# POV.net
KiCad netlist of a schematic drawn in EAGLE
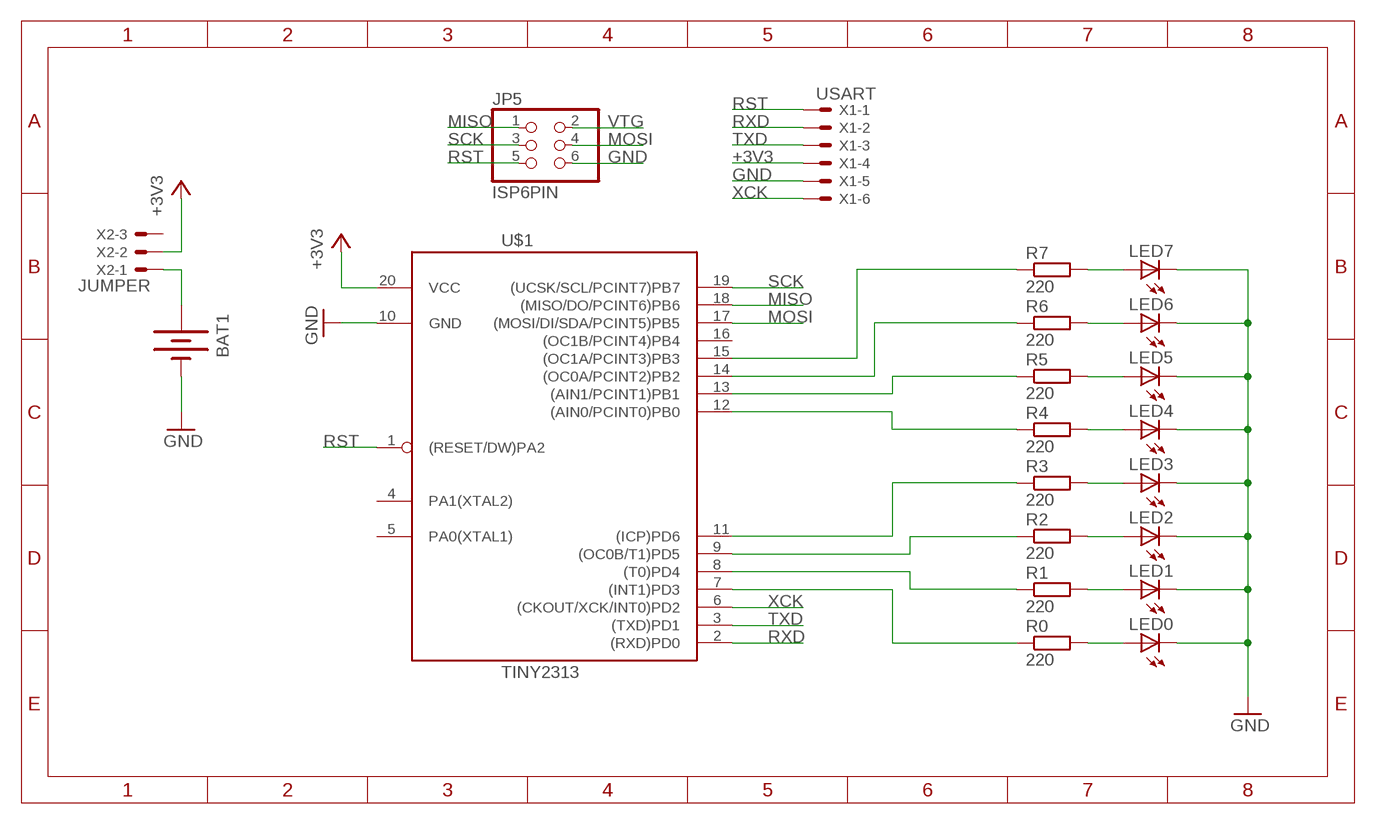
[diagram p0: schematic, sheet 1]

(export (version "E")
  (design (tool "Eeschema 10.0.6"))
  (components
    (comp (ref "BAT1")
      (value "BATTERY20PTH")
      (footprint "eagle-import:BATTCOM_20MM_PTH")
      (libsource (lib "eagle-import") (part "BATTERY20PTH"))
    )
    (comp (ref "JP5")
      (value "ISP6PIN")
      (footprint "eagle-import:2X03")
      (libsource (lib "eagle-import") (part "PINHD-2X3"))
    )
    (comp (ref "LED0")
      (value "LED3MM")
      (footprint "eagle-import:LED3MM")
      (libsource (lib "eagle-import") (part "LED3MM"))
    )
    (comp (ref "LED1")
      (value "LED3MM")
      (footprint "eagle-import:LED3MM")
      (libsource (lib "eagle-import") (part "LED3MM"))
    )
    (comp (ref "LED2")
      (value "LED3MM")
      (footprint "eagle-import:LED3MM")
      (libsource (lib "eagle-import") (part "LED3MM"))
    )
    (comp (ref "LED3")
      (value "LED3MM")
      (footprint "eagle-import:LED3MM")
      (libsource (lib "eagle-import") (part "LED3MM"))
    )
    (comp (ref "LED4")
      (value "LED3MM")
      (footprint "eagle-import:LED3MM")
      (libsource (lib "eagle-import") (part "LED3MM"))
    )
    (comp (ref "LED5")
      (value "LED3MM")
      (footprint "eagle-import:LED3MM")
      (libsource (lib "eagle-import") (part "LED3MM"))
    )
    (comp (ref "LED6")
      (value "LED3MM")
      (footprint "eagle-import:LED3MM")
      (libsource (lib "eagle-import") (part "LED3MM"))
    )
    (comp (ref "LED7")
      (value "LED3MM")
      (footprint "eagle-import:LED3MM")
      (libsource (lib "eagle-import") (part "LED3MM"))
    )
    (comp (ref "R0")
      (value "220")
      (footprint "eagle-import:0207_10")
      (libsource (lib "eagle-import") (part "R-EU_0207/10"))
    )
    (comp (ref "R1")
      (value "220")
      (footprint "eagle-import:0207_10")
      (libsource (lib "eagle-import") (part "R-EU_0207/10"))
    )
    (comp (ref "R2")
      (value "220")
      (footprint "eagle-import:0207_10")
      (libsource (lib "eagle-import") (part "R-EU_0207/10"))
    )
    (comp (ref "R3")
      (value "220")
      (footprint "eagle-import:0207_10")
      (libsource (lib "eagle-import") (part "R-EU_0207/10"))
    )
    (comp (ref "R4")
      (value "220")
      (footprint "eagle-import:0207_10")
      (libsource (lib "eagle-import") (part "R-EU_0207/10"))
    )
    (comp (ref "R5")
      (value "220")
      (footprint "eagle-import:0207_10")
      (libsource (lib "eagle-import") (part "R-EU_0207/10"))
    )
    (comp (ref "R6")
      (value "220")
      (footprint "eagle-import:0207_10")
      (libsource (lib "eagle-import") (part "R-EU_0207/10"))
    )
    (comp (ref "R7")
      (value "220")
      (footprint "eagle-import:0207_10")
      (libsource (lib "eagle-import") (part "R-EU_0207/10"))
    )
    (comp (ref "U$1")
      (value "TINY2313")
      (footprint "eagle-import:DIL20")
      (libsource (lib "eagle-import") (part "TINY2313"))
    )
    (comp (ref "X1")
      (value "USART")
      (footprint "eagle-import:22-23-2061")
      (fields (field (name "MF") "MOLEX") (field (name "MPN") "22-23-2061"))
      (libsource (lib "eagle-import") (part "22-23-2061"))
    )
    (comp (ref "X2")
      (value "JUMPER")
      (footprint "eagle-import:22-23-2031")
      (fields (field (name "MF") "MOLEX") (field (name "MPN") "22-23-2031"))
      (libsource (lib "eagle-import") (part "22-23-2031"))
    )
  )
  (nets
    (net (code "1") (name "+3V3") (class "Default")
      (node (ref "U$1") (pin "20") (pinfunction "VCC_20") (pintype "power_in"))
      (node (ref "X1") (pin "4") (pinfunction "S_4") (pintype "passive"))
      (node (ref "X2") (pin "2") (pinfunction "S_2") (pintype "passive"))
    )
    (net (code "2") (name "/MISO") (class "Default")
      (node (ref "JP5") (pin "1") (pinfunction "1_1") (pintype "passive"))
      (node (ref "U$1") (pin "18") (pinfunction "(MISO/DO/PCINT6)PB6_18") (pintype "bidirectional"))
    )
    (net (code "3") (name "/MOSI") (class "Default")
      (node (ref "JP5") (pin "4") (pinfunction "4_4") (pintype "passive"))
      (node (ref "U$1") (pin "17") (pinfunction "(MOSI/DI/SDA/PCINT5)PB5_17") (pintype "bidirectional"))
    )
    (net (code "4") (name "/RST") (class "Default")
      (node (ref "JP5") (pin "5") (pinfunction "5_5") (pintype "passive"))
      (node (ref "U$1") (pin "1") (pinfunction "(RESET/DW)PA2_1") (pintype "input"))
      (node (ref "X1") (pin "1") (pinfunction "S_1") (pintype "passive"))
    )
    (net (code "5") (name "/RXD") (class "Default")
      (node (ref "U$1") (pin "2") (pinfunction "(RXD)PD0_2") (pintype "bidirectional"))
      (node (ref "X1") (pin "2") (pinfunction "S_2") (pintype "passive"))
    )
    (net (code "6") (name "/SCK") (class "Default")
      (node (ref "JP5") (pin "3") (pinfunction "3_3") (pintype "passive"))
      (node (ref "U$1") (pin "19") (pinfunction "(UCSK/SCL/PCINT7)PB7_19") (pintype "bidirectional"))
    )
    (net (code "7") (name "/TXD") (class "Default")
      (node (ref "U$1") (pin "3") (pinfunction "(TXD)PD1_3") (pintype "bidirectional"))
      (node (ref "X1") (pin "3") (pinfunction "S_3") (pintype "passive"))
    )
    (net (code "8") (name "/VTG") (class "Default")
      (node (ref "JP5") (pin "2") (pinfunction "2_2") (pintype "passive"))
    )
    (net (code "9") (name "/XCK") (class "Default")
      (node (ref "U$1") (pin "6") (pinfunction "(CKOUT/XCK/INT0)PD2_6") (pintype "bidirectional"))
      (node (ref "X1") (pin "6") (pinfunction "S_6") (pintype "passive"))
    )
    (net (code "10") (name "GND") (class "Default")
      (node (ref "BAT1") (pin "2") (pinfunction "-_2") (pintype "power_in"))
      (node (ref "JP5") (pin "6") (pinfunction "6_6") (pintype "passive"))
      (node (ref "LED0") (pin "K") (pinfunction "C_K") (pintype "passive"))
      (node (ref "LED1") (pin "K") (pinfunction "C_K") (pintype "passive"))
      (node (ref "LED2") (pin "K") (pinfunction "C_K") (pintype "passive"))
      (node (ref "LED3") (pin "K") (pinfunction "C_K") (pintype "passive"))
      (node (ref "LED4") (pin "K") (pinfunction "C_K") (pintype "passive"))
      (node (ref "LED5") (pin "K") (pinfunction "C_K") (pintype "passive"))
      (node (ref "LED6") (pin "K") (pinfunction "C_K") (pintype "passive"))
      (node (ref "LED7") (pin "K") (pinfunction "C_K") (pintype "passive"))
      (node (ref "U$1") (pin "10") (pinfunction "GND_10") (pintype "power_in"))
      (node (ref "X1") (pin "5") (pinfunction "S_5") (pintype "passive"))
    )
    (net (code "11") (name "Net-(BAT1-+)") (class "Default")
      (node (ref "BAT1") (pin "1") (pinfunction "+_1") (pintype "power_in"))
      (node (ref "X2") (pin "1") (pinfunction "S_1") (pintype "passive"))
    )
    (net (code "12") (name "Net-(LED0-PadA)") (class "Default")
      (node (ref "LED0") (pin "A") (pinfunction "A_A") (pintype "passive"))
      (node (ref "R0") (pin "2") (pinfunction "2_2") (pintype "passive"))
    )
    (net (code "13") (name "Net-(LED1-PadA)") (class "Default")
      (node (ref "LED1") (pin "A") (pinfunction "A_A") (pintype "passive"))
      (node (ref "R1") (pin "2") (pinfunction "2_2") (pintype "passive"))
    )
    (net (code "14") (name "Net-(LED2-PadA)") (class "Default")
      (node (ref "LED2") (pin "A") (pinfunction "A_A") (pintype "passive"))
      (node (ref "R2") (pin "2") (pinfunction "2_2") (pintype "passive"))
    )
    (net (code "15") (name "Net-(LED3-PadA)") (class "Default")
      (node (ref "LED3") (pin "A") (pinfunction "A_A") (pintype "passive"))
      (node (ref "R3") (pin "2") (pinfunction "2_2") (pintype "passive"))
    )
    (net (code "16") (name "Net-(LED4-PadA)") (class "Default")
      (node (ref "LED4") (pin "A") (pinfunction "A_A") (pintype "passive"))
      (node (ref "R4") (pin "2") (pinfunction "2_2") (pintype "passive"))
    )
    (net (code "17") (name "Net-(LED5-PadA)") (class "Default")
      (node (ref "LED5") (pin "A") (pinfunction "A_A") (pintype "passive"))
      (node (ref "R5") (pin "2") (pinfunction "2_2") (pintype "passive"))
    )
    (net (code "18") (name "Net-(LED6-PadA)") (class "Default")
      (node (ref "LED6") (pin "A") (pinfunction "A_A") (pintype "passive"))
      (node (ref "R6") (pin "2") (pinfunction "2_2") (pintype "passive"))
    )
    (net (code "19") (name "Net-(LED7-PadA)") (class "Default")
      (node (ref "LED7") (pin "A") (pinfunction "A_A") (pintype "passive"))
      (node (ref "R7") (pin "2") (pinfunction "2_2") (pintype "passive"))
    )
    (net (code "20") (name "Net-(U$1-(AIN0{slash}PCINT0)PB0)") (class "Default")
      (node (ref "R4") (pin "1") (pinfunction "1_1") (pintype "passive"))
      (node (ref "U$1") (pin "12") (pinfunction "(AIN0/PCINT0)PB0_12") (pintype "bidirectional"))
    )
    (net (code "21") (name "Net-(U$1-(AIN1{slash}PCINT1)PB1)") (class "Default")
      (node (ref "R5") (pin "1") (pinfunction "1_1") (pintype "passive"))
      (node (ref "U$1") (pin "13") (pinfunction "(AIN1/PCINT1)PB1_13") (pintype "bidirectional"))
    )
    (net (code "22") (name "Net-(U$1-(ICP)PD6)") (class "Default")
      (node (ref "R3") (pin "1") (pinfunction "1_1") (pintype "passive"))
      (node (ref "U$1") (pin "11") (pinfunction "(ICP)PD6_11") (pintype "bidirectional"))
    )
    (net (code "23") (name "Net-(U$1-(INT1)PD3)") (class "Default")
      (node (ref "R0") (pin "1") (pinfunction "1_1") (pintype "passive"))
      (node (ref "U$1") (pin "7") (pinfunction "(INT1)PD3_7") (pintype "bidirectional"))
    )
    (net (code "24") (name "Net-(U$1-(OC0A{slash}PCINT2)PB2)") (class "Default")
      (node (ref "R6") (pin "1") (pinfunction "1_1") (pintype "passive"))
      (node (ref "U$1") (pin "14") (pinfunction "(OC0A/PCINT2)PB2_14") (pintype "bidirectional"))
    )
    (net (code "25") (name "Net-(U$1-(OC0B{slash}T1)PD5)") (class "Default")
      (node (ref "R2") (pin "1") (pinfunction "1_1") (pintype "passive"))
      (node (ref "U$1") (pin "9") (pinfunction "(OC0B/T1)PD5_9") (pintype "bidirectional"))
    )
    (net (code "26") (name "Net-(U$1-(OC1A{slash}PCINT3)PB3)") (class "Default")
      (node (ref "R7") (pin "1") (pinfunction "1_1") (pintype "passive"))
      (node (ref "U$1") (pin "15") (pinfunction "(OC1A/PCINT3)PB3_15") (pintype "bidirectional"))
    )
    (net (code "27") (name "Net-(U$1-(T0)PD4)") (class "Default")
      (node (ref "R1") (pin "1") (pinfunction "1_1") (pintype "passive"))
      (node (ref "U$1") (pin "8") (pinfunction "(T0)PD4_8") (pintype "bidirectional"))
    )
    (net (code "28") (name "unconnected-(U$1-(OC1B{slash}PCINT4)PB4-Pad16)") (class "Default")
      (node (ref "U$1") (pin "16") (pinfunction "(OC1B/PCINT4)PB4_16") (pintype "bidirectional"))
    )
    (net (code "29") (name "unconnected-(U$1-PA0(XTAL1)-Pad5)") (class "Default")
      (node (ref "U$1") (pin "5") (pinfunction "PA0(XTAL1)_5") (pintype "bidirectional"))
    )
    (net (code "30") (name "unconnected-(U$1-PA1(XTAL2)-Pad4)") (class "Default")
      (node (ref "U$1") (pin "4") (pinfunction "PA1(XTAL2)_4") (pintype "bidirectional"))
    )
    (net (code "31") (name "unconnected-(X2C-S-Pad3)") (class "Default")
      (node (ref "X2") (pin "3") (pinfunction "S_3") (pintype "passive"))
    )
  )
)
